# LiPo_BMS.net
KiCad netlist of a schematic drawn in Altium Designer
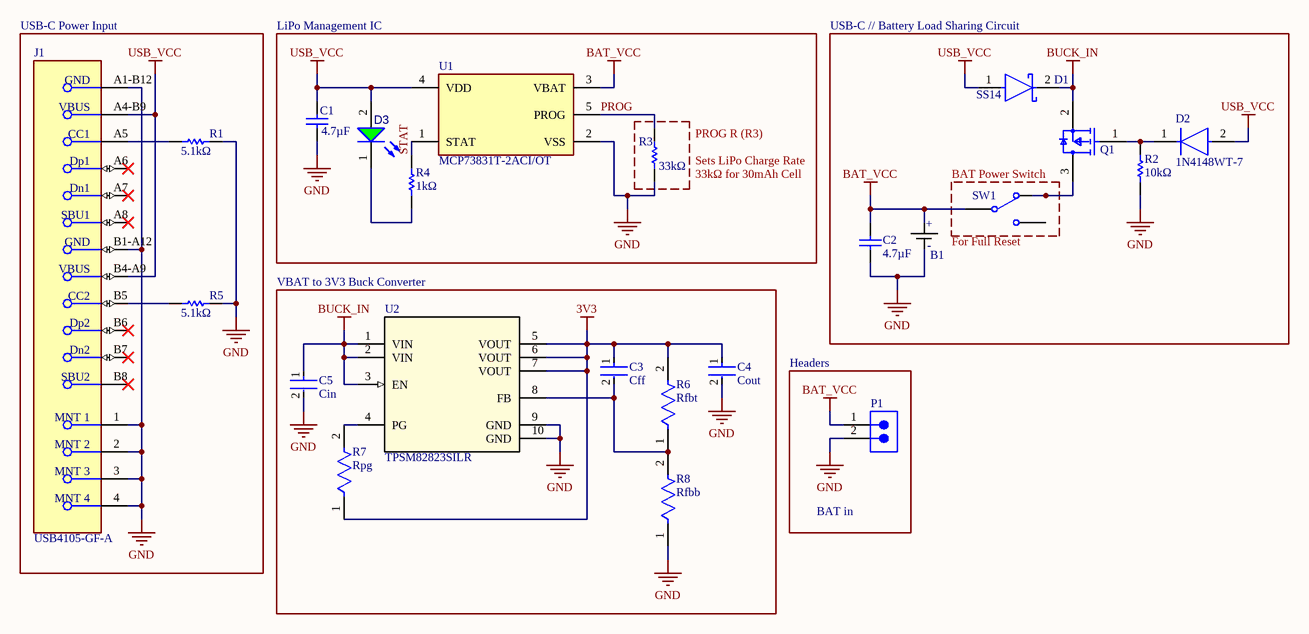
[diagram p0: LiPo BMS.SchDoc]

(export (version "E")
  (design (tool "Eeschema 10.0.6"))
  (components
    (comp (ref "B1") (value "LiPo") (libsource (lib "LiPoSchematicLibrary") (part "3.7V 30mAh LiPo")))
    (comp (ref "C1")
      (value "4.7µF")
      (footprint "CAPC1206(3216)190_L")
      (description "CAP 4.7uF 25V ±5% 1206 (3216 Metric) Thickness 1.9mm SMD")
      (fields (field (name "TOLERANCE") "Â±5%"))
      (libsource (lib "Altium Content Vault") (part "CAP"))
    )
    (comp (ref "C2")
      (value "4.7µF")
      (footprint "CAPC1206(3216)190_L")
      (description "CAP 4.7uF 25V ±5% 1206 (3216 Metric) Thickness 1.9mm SMD")
      (fields (field (name "TOLERANCE") "Â±5%"))
      (libsource (lib "Altium Content Vault") (part "CAP"))
    )
    (comp (ref "C3")
      (value "Cff")
      (footprint "FP-GRM033-0_03-IPC_A")
      (description "Chip Multilayer Ceramic Capacitors for General Purpose, 0201, 120pF, X7R, 15%, 10%, 25V")
      (fields (field (name "TOLERANCE") "10%"))
      (libsource (lib "Altium Content Vault") (part "b4654b650e69147ec39a6b967a45e02"))
    )
    (comp (ref "C4")
      (value "Cout")
      (footprint "FP-C0805C-DG-MFG")
      (description "CAP CER 10UF 10V X5R 0805")
      (fields (field (name "TOLERANCE") "10%") (field (name "MANUFACTURER PART NUMBER") "C0805C106K8PACTU"))
      (libsource (lib "Altium Content Vault") (part "11868f565c42a9108669ba33697ecf6"))
    )
    (comp (ref "C5")
      (value "Cin")
      (footprint "FP-GRM188-0_1-e0_2_0_55-IPC_A")
      (description "Chip Multilayer Ceramic Capacitors for General Purpose, 0603, 10uF, X5R, 15%, 20%, 6.3V")
      (fields (field (name "VOLTAGE") "6.3V") (field (name "TOLERANCE") "20%"))
      (libsource (lib "Altium Content Vault") (part "02cd4be3c70576c341d710602a673aa"))
    )
    (comp (ref "D1")
      (value "SS14")
      (footprint "FP-403AE-MFG")
      (description "DIODE SCHOTTKY 40V 1A SMA")
      (fields
        (field (name "MANUFACTURER") "ON Semiconductor")
        (field (name "OCTOPART") "https://octopart.com/ss14-on+semiconductor-29205033")
      )
      (libsource (lib "Altium Content Vault") (part "360ad2f4ac25a952324d13796385471"))
    )
    (comp (ref "D2")
      (value "1N4148WT-7")
      (footprint "FP-SOD523-MFG")
      (description "DIODE GEN PURP 80V 125MA SOD523")
      (libsource (lib "Altium Content Vault") (part "d7152d700b627762746794eb795d46e"))
    )
    (comp (ref "D3")
      (value "150120GS75000")
      (footprint "WL-SMCW_1206_150120xx75000")
      (description "WL-SMCW SMT Mono-Color Chip LED Waterclear")
      (libsource (lib "Altium Content Vault") (part "LED_Green_2A-1K"))
    )
    (comp (ref "J1")
      (value "USB4105-GF-A")
      (footprint "FP-USB4105-GF-A-MFG")
      (description "CONN RCPT USB2.0 TYPEC 5A")
      (fields
        (field (name "MANUFACTURER") "GCT")
        (field (name "OCTOPART") "https://octopart.com/usb4105-gf-a-gct-106627878")
      )
      (libsource (lib "Altium Content Vault") (part "e7c17a616881a82b79941196b4bec10"))
    )
    (comp (ref "P1")
      (value "61300211121")
      (footprint "61300211121")
      (libsource (lib "Altium Content Vault") (part "Header_Male_1R_02P"))
    )
    (comp (ref "Q1")
      (value "IRLML6402TRPBF")
      (footprint "FP-Micro3-MFG")
      (description "MOSFET P-CH 20V 3.7A SOT-23")
      (fields
        (field (name "OCTOPART") "https://octopart.com/irlml6402trpbf-infineon-65874989")
        (field (name "MANUFACTURER") "Infineon")
      )
      (libsource (lib "Altium Content Vault") (part "566027c8dc92b5207d53ac25ab3eb60"))
    )
    (comp (ref "R1")
      (value "5.1kΩ")
      (footprint "RESC3116X65X40LL10T20")
      (fields (field (name "MANUFACTURER") "Yageo") (field (name "PART NUMBER") "RC1206JR-075K1L"))
      (libsource (lib "Altium Content Vault") (part "RES"))
    )
    (comp (ref "R2")
      (value "10kΩ")
      (footprint "RESC3116X65X40LL10T20")
      (description "Chip Resistor, 10 KOhm, +/- 1%, 0.25 W, -55 to 155 degC, 1206 (3216 Metric), RoHS, Tape and Reel")
      (fields (field (name "TOLERANCE") "1%") (field (name "MANUFACTURER") "Yageo"))
      (libsource (lib "Altium Content Vault") (part "RES-2"))
    )
    (comp (ref "R3")
      (value "33kΩ")
      (footprint "RESC3116X65X40LL10T20")
      (fields (field (name "PART NUMBER") "RC1206JR-1033KL") (field (name "MANUFACTURER") "Yageo"))
      (libsource (lib "Altium Content Vault") (part "RES"))
    )
    (comp (ref "R4")
      (value "1kΩ")
      (footprint "RESC3116X65X40LL10T20")
      (description "Chip Resistor, 1 KOhm, +/- 1%, 0.25 W, -55 to 155 degC, 1206 (3216 Metric), RoHS, Tape and Reel")
      (fields (field (name "TOLERANCE") "1%") (field (name "MANUFACTURER") "Yageo"))
      (libsource (lib "Altium Content Vault") (part "RES-2"))
    )
    (comp (ref "R5")
      (value "5.1kΩ")
      (footprint "RESC3116X65X40LL10T20")
      (fields (field (name "MANUFACTURER") "Yageo") (field (name "PART NUMBER") "RC1206JR-075K1L"))
      (libsource (lib "Altium Content Vault") (part "RES"))
    )
    (comp (ref "R6")
      (value "Rfbt")
      (footprint "FP-CRCW0402-e3-MFG")
      (description "RES Thick Film, 453kΩ, 1%, 0.063W, 100ppm/°C, 0402")
      (fields (field (name "TOLERANCE") "1%"))
      (libsource (lib "Altium Content Vault") (part "1029c3af85768c4190bb7ad29bc67b5"))
    )
    (comp (ref "R7")
      (value "Rpg")
      (footprint "FP-CRCW0402-e3-IPC_C")
      (description "RES Thick Film, 100kΩ, 1%, 0.063W, 100ppm/°C, 0402")
      (fields (field (name "TOLERANCE") "1%"))
      (libsource (lib "Altium Content Vault") (part "1029c3af85768c4190bb7ad29bc67b5"))
    )
    (comp (ref "R8")
      (value "Rfbb")
      (footprint "FP-CRCW0402-e3-IPC_C")
      (description "RES Thick Film, 100kΩ, 1%, 0.063W, 100ppm/°C, 0402")
      (fields (field (name "TOLERANCE") "1%"))
      (libsource (lib "Altium Content Vault") (part "1029c3af85768c4190bb7ad29bc67b5"))
    )
    (comp (ref "SW1")
      (value "450404015514")
      (footprint "450404015514")
      (description "450404015514 Slide Switch, 0.3A, 5Vdc, Smd Rohs Compliant: Yes")
      (libsource (lib "Altium Content Vault") (part "SPDT"))
    )
    (comp (ref "U1")
      (value "MCP73831T-2ACI/OT")
      (footprint "FP-C04-091-OT-IPC_B")
      (description "IC CONTROLLR LI-ION 4.2V SOT23-5")
      (libsource (lib "Altium Content Vault") (part "61f5a3bb3429d9e0caadea342aa3b19"))
    )
    (comp (ref "U2")
      (value "TPSM82823SILR")
      (footprint "SIL0010D-MFG")
      (description "No Description Available")
      (libsource (lib "TPSM82823SILR") (part "TPSM82823SILR"))
    )
  )
  (nets
    (net (code "1") (name "/PROG") (class "Default")
      (node (ref "R3") (pin "2") (pinfunction "2_2") (pintype "passive"))
      (node (ref "U1") (pin "5") (pinfunction "PROG_5") (pintype "passive"))
    )
    (net (code "2") (name "/STAT") (class "Default")
      (node (ref "R4") (pin "1") (pinfunction "1_1") (pintype "passive"))
      (node (ref "U1") (pin "1") (pinfunction "STAT_1") (pintype "passive"))
    )
    (net (code "3") (name "3V3") (class "Default")
      (node (ref "C3") (pin "1") (pinfunction "1_1") (pintype "passive"))
      (node (ref "C4") (pin "1") (pinfunction "1_1") (pintype "passive"))
      (node (ref "R6") (pin "2") (pinfunction "2_2") (pintype "passive"))
      (node (ref "R7") (pin "1") (pinfunction "1_1") (pintype "passive"))
      (node (ref "U2") (pin "5") (pinfunction "VOUT_5") (pintype "power_in"))
      (node (ref "U2") (pin "6") (pinfunction "VOUT_6") (pintype "power_in"))
      (node (ref "U2") (pin "7") (pinfunction "VOUT_7") (pintype "power_in"))
    )
    (net (code "4") (name "BAT_VCC") (class "Default")
      (node (ref "B1") (pin "0") (pinfunction "+_0") (pintype "passive"))
      (node (ref "C2") (pin "2") (pinfunction "2_2") (pintype "passive"))
      (node (ref "P1") (pin "1") (pinfunction "1_1") (pintype "passive"))
      (node (ref "SW1") (pin "COM") (pinfunction "COM_COM") (pintype "passive"))
      (node (ref "U1") (pin "3") (pinfunction "VBAT_3") (pintype "power_in"))
    )
    (net (code "5") (name "BUCK_IN") (class "Default")
      (node (ref "C5") (pin "1") (pinfunction "1_1") (pintype "passive"))
      (node (ref "D1") (pin "2") (pinfunction "C_2") (pintype "passive"))
      (node (ref "Q1") (pin "2") (pinfunction "S_2") (pintype "passive"))
      (node (ref "U2") (pin "1") (pinfunction "VIN_1") (pintype "power_in"))
      (node (ref "U2") (pin "2") (pinfunction "VIN_2") (pintype "power_in"))
      (node (ref "U2") (pin "3") (pinfunction "EN_3") (pintype "input"))
    )
    (net (code "6") (name "GND") (class "Default")
      (node (ref "B1") (pin "1") (pinfunction "-_1") (pintype "passive"))
      (node (ref "C1") (pin "1") (pinfunction "1_1") (pintype "passive"))
      (node (ref "C2") (pin "1") (pinfunction "1_1") (pintype "passive"))
      (node (ref "C4") (pin "2") (pinfunction "2_2") (pintype "passive"))
      (node (ref "C5") (pin "2") (pinfunction "2_2") (pintype "passive"))
      (node (ref "J1") (pin "1") (pinfunction "MNT_1_1") (pintype "power_in"))
      (node (ref "J1") (pin "2") (pinfunction "MNT_2_2") (pintype "power_in"))
      (node (ref "J1") (pin "3") (pinfunction "MNT_3_3") (pintype "power_in"))
      (node (ref "J1") (pin "4") (pinfunction "MNT_4_4") (pintype "power_in"))
      (node (ref "J1") (pin "A1-B12") (pinfunction "GND_A1-B12") (pintype "power_in"))
      (node (ref "J1") (pin "B1-A12") (pinfunction "GND_B1-A12") (pintype "bidirectional"))
      (node (ref "P1") (pin "2") (pinfunction "2_2") (pintype "passive"))
      (node (ref "R1") (pin "2") (pinfunction "2_2") (pintype "passive"))
      (node (ref "R2") (pin "1") (pinfunction "1_1") (pintype "passive"))
      (node (ref "R3") (pin "1") (pinfunction "1_1") (pintype "passive"))
      (node (ref "R5") (pin "2") (pinfunction "2_2") (pintype "passive"))
      (node (ref "R8") (pin "1") (pinfunction "1_1") (pintype "passive"))
      (node (ref "U1") (pin "2") (pinfunction "VSS_2") (pintype "power_in"))
      (node (ref "U2") (pin "10") (pinfunction "GND_10") (pintype "power_in"))
      (node (ref "U2") (pin "9") (pinfunction "GND_9") (pintype "power_in"))
    )
    (net (code "7") (name "Net-(D2-C)") (class "Default")
      (node (ref "D2") (pin "1") (pinfunction "C_1") (pintype "passive"))
      (node (ref "Q1") (pin "1") (pinfunction "G_1") (pintype "passive"))
      (node (ref "R2") (pin "2") (pinfunction "2_2") (pintype "passive"))
    )
    (net (code "8") (name "Net-(D3-K)") (class "Default")
      (node (ref "D3") (pin "1") (pinfunction "K_1") (pintype "passive"))
      (node (ref "R4") (pin "2") (pinfunction "2_2") (pintype "passive"))
    )
    (net (code "9") (name "Net-(J1-CC1)") (class "Default")
      (node (ref "J1") (pin "A5") (pinfunction "CC1_A5") (pintype "power_in"))
      (node (ref "R1") (pin "1") (pinfunction "1_1") (pintype "passive"))
    )
    (net (code "10") (name "Net-(J1-CC2)") (class "Default")
      (node (ref "J1") (pin "B5") (pinfunction "CC2_B5") (pintype "bidirectional"))
      (node (ref "R5") (pin "1") (pinfunction "1_1") (pintype "passive"))
    )
    (net (code "11") (name "Net-(Q1-D)") (class "Default")
      (node (ref "Q1") (pin "3") (pinfunction "D_3") (pintype "passive"))
      (node (ref "SW1") (pin "L1") (pinfunction "L1_L1") (pintype "passive"))
    )
    (net (code "12") (name "Net-(U2-FB)") (class "Default")
      (node (ref "C3") (pin "2") (pinfunction "2_2") (pintype "passive"))
      (node (ref "R6") (pin "1") (pinfunction "1_1") (pintype "passive"))
      (node (ref "R8") (pin "2") (pinfunction "2_2") (pintype "passive"))
      (node (ref "U2") (pin "8") (pinfunction "FB_8") (pintype "passive"))
    )
    (net (code "13") (name "Net-(U2-PG)") (class "Default")
      (node (ref "R7") (pin "2") (pinfunction "2_2") (pintype "passive"))
      (node (ref "U2") (pin "4") (pinfunction "PG_4") (pintype "open_collector"))
    )
    (net (code "14") (name "USB_VCC") (class "Default")
      (node (ref "C1") (pin "2") (pinfunction "2_2") (pintype "passive"))
      (node (ref "D1") (pin "1") (pinfunction "A_1") (pintype "passive"))
      (node (ref "D2") (pin "2") (pinfunction "A_2") (pintype "passive"))
      (node (ref "D3") (pin "2") (pinfunction "A_2") (pintype "passive"))
      (node (ref "J1") (pin "A4-B9") (pinfunction "VBUS_A4-B9") (pintype "power_in"))
      (node (ref "J1") (pin "B4-A9") (pinfunction "VBUS_B4-A9") (pintype "bidirectional"))
      (node (ref "U1") (pin "4") (pinfunction "VDD_4") (pintype "power_in"))
    )
    (net (code "15") (name "unconnected-(J1-Dn1-PadA7)") (class "Default")
      (node (ref "J1") (pin "A7") (pinfunction "Dn1_A7") (pintype "bidirectional+no_connect"))
    )
    (net (code "16") (name "unconnected-(J1-Dn2-PadB7)") (class "Default")
      (node (ref "J1") (pin "B7") (pinfunction "Dn2_B7") (pintype "bidirectional+no_connect"))
    )
    (net (code "17") (name "unconnected-(J1-Dp1-PadA6)") (class "Default")
      (node (ref "J1") (pin "A6") (pinfunction "Dp1_A6") (pintype "bidirectional+no_connect"))
    )
    (net (code "18") (name "unconnected-(J1-Dp2-PadB6)") (class "Default")
      (node (ref "J1") (pin "B6") (pinfunction "Dp2_B6") (pintype "bidirectional+no_connect"))
    )
    (net (code "19") (name "unconnected-(J1-SBU1-PadA8)") (class "Default")
      (node (ref "J1") (pin "A8") (pinfunction "SBU1_A8") (pintype "bidirectional+no_connect"))
    )
    (net (code "20") (name "unconnected-(J1-SBU2-PadB8)") (class "Default")
      (node (ref "J1") (pin "B8") (pinfunction "SBU2_B8") (pintype "power_in+no_connect"))
    )
    (net (code "21") (name "unconnected-(SW1-PadL2)") (class "Default")
      (node (ref "SW1") (pin "L2") (pinfunction "L2_L2") (pintype "passive"))
    )
  )
)
